# design.net
KiCad netlist of a schematic drawn in Altium Designer
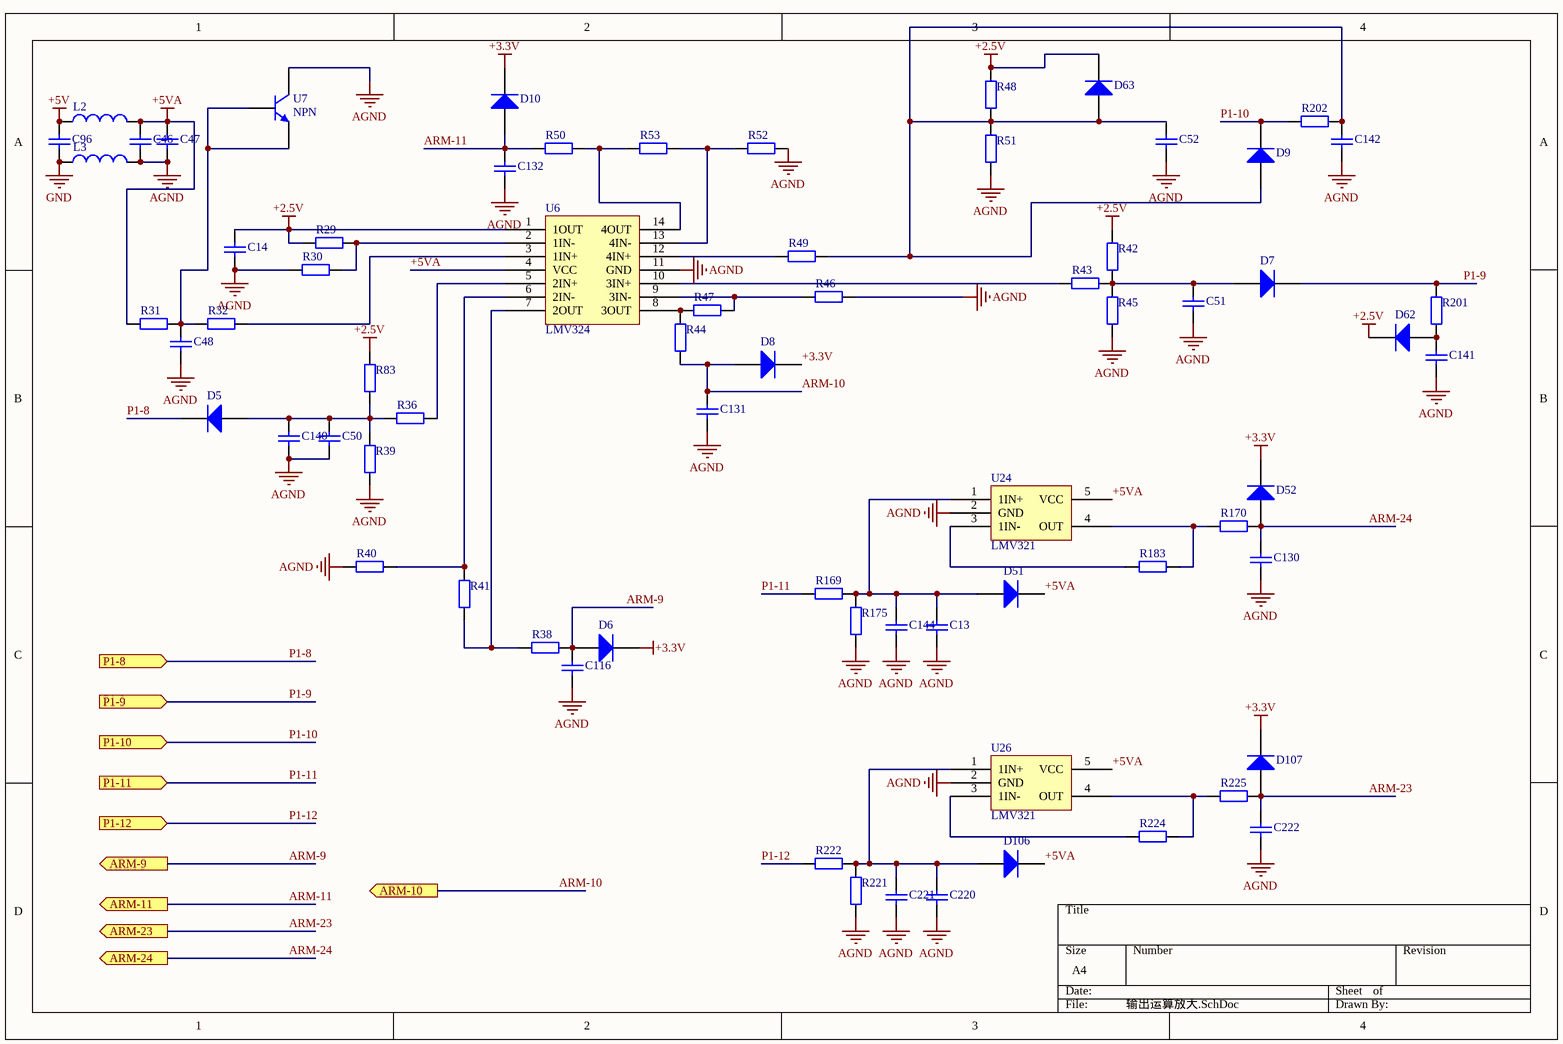
[diagram p0: 输出运算放大.SchDoc]

(export (version "E")
  (design (tool "Eeschema 10.0.6"))
  (components
    (comp (ref "C13")
      (value "Cap")
      (footprint "RAD-0.3")
      (description "Capacitor")
      (fields (field (name "PUBLISHER") "Altium Limited"))
      (libsource (lib "Miscellaneous Devices") (part "Cap"))
    )
    (comp (ref "C14")
      (value "Cap")
      (footprint "RAD-0.3")
      (description "Capacitor")
      (fields (field (name "PUBLISHER") "Altium Limited"))
      (libsource (lib "Miscellaneous Devices") (part "Cap"))
    )
    (comp (ref "C46")
      (value "Cap")
      (footprint "RAD-0.3")
      (description "Capacitor")
      (fields (field (name "PUBLISHER") "Altium Limited"))
      (libsource (lib "Miscellaneous Devices") (part "Cap"))
    )
    (comp (ref "C47")
      (value "Cap")
      (footprint "RAD-0.3")
      (description "Capacitor")
      (fields (field (name "PUBLISHER") "Altium Limited"))
      (libsource (lib "Miscellaneous Devices") (part "Cap"))
    )
    (comp (ref "C48")
      (value "Cap")
      (footprint "RAD-0.3")
      (description "Capacitor")
      (fields (field (name "PUBLISHER") "Altium Limited"))
      (libsource (lib "Miscellaneous Devices") (part "Cap"))
    )
    (comp (ref "C50")
      (value "Cap")
      (footprint "RAD-0.3")
      (description "Capacitor")
      (fields (field (name "PUBLISHER") "Altium Limited"))
      (libsource (lib "Miscellaneous Devices") (part "Cap"))
    )
    (comp (ref "C51")
      (value "Cap")
      (footprint "RAD-0.3")
      (description "Capacitor")
      (fields (field (name "PUBLISHER") "Altium Limited"))
      (libsource (lib "Miscellaneous Devices") (part "Cap"))
    )
    (comp (ref "C52")
      (value "Cap")
      (footprint "RAD-0.3")
      (description "Capacitor")
      (fields (field (name "PUBLISHER") "Altium Limited"))
      (libsource (lib "Miscellaneous Devices") (part "Cap"))
    )
    (comp (ref "C96")
      (value "Cap")
      (footprint "RAD-0.3")
      (description "Capacitor")
      (fields (field (name "PUBLISHER") "Altium Limited"))
      (libsource (lib "Miscellaneous Devices") (part "Cap"))
    )
    (comp (ref "C116")
      (value "Cap")
      (footprint "RAD-0.3")
      (description "Capacitor")
      (fields (field (name "PUBLISHER") "Altium Limited"))
      (libsource (lib "Miscellaneous Devices") (part "Cap"))
    )
    (comp (ref "C130")
      (value "Cap")
      (footprint "RAD-0.3")
      (description "Capacitor")
      (fields (field (name "PUBLISHER") "Altium Limited"))
      (libsource (lib "Miscellaneous Devices") (part "Cap"))
    )
    (comp (ref "C131")
      (value "Cap")
      (footprint "RAD-0.3")
      (description "Capacitor")
      (fields (field (name "PUBLISHER") "Altium Limited"))
      (libsource (lib "Miscellaneous Devices") (part "Cap"))
    )
    (comp (ref "C132")
      (value "Cap")
      (footprint "RAD-0.3")
      (description "Capacitor")
      (fields (field (name "PUBLISHER") "Altium Limited"))
      (libsource (lib "Miscellaneous Devices") (part "Cap"))
    )
    (comp (ref "C140")
      (value "Cap")
      (footprint "RAD-0.3")
      (description "Capacitor")
      (fields (field (name "PUBLISHER") "Altium Limited"))
      (libsource (lib "Miscellaneous Devices") (part "Cap"))
    )
    (comp (ref "C141")
      (value "Cap")
      (footprint "RAD-0.3")
      (description "Capacitor")
      (fields (field (name "PUBLISHER") "Altium Limited"))
      (libsource (lib "Miscellaneous Devices") (part "Cap"))
    )
    (comp (ref "C142")
      (value "Cap")
      (footprint "RAD-0.3")
      (description "Capacitor")
      (fields (field (name "PUBLISHER") "Altium Limited"))
      (libsource (lib "Miscellaneous Devices") (part "Cap"))
    )
    (comp (ref "C144")
      (value "Cap")
      (footprint "RAD-0.3")
      (description "Capacitor")
      (fields (field (name "PUBLISHER") "Altium Limited"))
      (libsource (lib "Miscellaneous Devices") (part "Cap"))
    )
    (comp (ref "C220")
      (value "Cap")
      (footprint "RAD-0.3")
      (description "Capacitor")
      (fields (field (name "PUBLISHER") "Altium Limited"))
      (libsource (lib "Miscellaneous Devices") (part "Cap"))
    )
    (comp (ref "C221")
      (value "Cap")
      (footprint "RAD-0.3")
      (description "Capacitor")
      (fields (field (name "PUBLISHER") "Altium Limited"))
      (libsource (lib "Miscellaneous Devices") (part "Cap"))
    )
    (comp (ref "C222")
      (value "Cap")
      (footprint "RAD-0.3")
      (description "Capacitor")
      (fields (field (name "PUBLISHER") "Altium Limited"))
      (libsource (lib "Miscellaneous Devices") (part "Cap"))
    )
    (comp (ref "D5")
      (value "Diode 1N4007")
      (footprint "DO-41")
      (description "1 Amp General Purpose Rectifier")
      (fields (field (name "PUBLISHER") "Altium Limited"))
      (libsource (lib "Miscellaneous Devices") (part "Diode 1N4007"))
    )
    (comp (ref "D6")
      (value "Diode 1N4007")
      (footprint "DO-41")
      (description "1 Amp General Purpose Rectifier")
      (fields (field (name "PUBLISHER") "Altium Limited"))
      (libsource (lib "Miscellaneous Devices") (part "Diode 1N4007"))
    )
    (comp (ref "D7")
      (value "Diode 1N4007")
      (footprint "DO-41")
      (description "1 Amp General Purpose Rectifier")
      (fields (field (name "PUBLISHER") "Altium Limited"))
      (libsource (lib "Miscellaneous Devices") (part "Diode 1N4007"))
    )
    (comp (ref "D8")
      (value "Diode 1N4007")
      (footprint "DO-41")
      (description "1 Amp General Purpose Rectifier")
      (fields (field (name "PUBLISHER") "Altium Limited"))
      (libsource (lib "Miscellaneous Devices") (part "Diode 1N4007"))
    )
    (comp (ref "D9")
      (value "Diode 1N4007")
      (footprint "DO-41")
      (description "1 Amp General Purpose Rectifier")
      (fields (field (name "PUBLISHER") "Altium Limited"))
      (libsource (lib "Miscellaneous Devices") (part "Diode 1N4007"))
    )
    (comp (ref "D10")
      (value "Diode 1N4007")
      (footprint "DO-41")
      (description "1 Amp General Purpose Rectifier")
      (fields (field (name "PUBLISHER") "Altium Limited"))
      (libsource (lib "Miscellaneous Devices") (part "Diode 1N4007"))
    )
    (comp (ref "D51")
      (value "Diode 1N4007")
      (footprint "DO-41")
      (description "1 Amp General Purpose Rectifier")
      (fields (field (name "PUBLISHER") "Altium Limited"))
      (libsource (lib "Miscellaneous Devices") (part "Diode 1N4007"))
    )
    (comp (ref "D52")
      (value "Diode 1N4007")
      (footprint "DO-41")
      (description "1 Amp General Purpose Rectifier")
      (fields (field (name "PUBLISHER") "Altium Limited"))
      (libsource (lib "Miscellaneous Devices") (part "Diode 1N4007"))
    )
    (comp (ref "D62")
      (value "Diode 1N4007")
      (footprint "DO-41")
      (description "1 Amp General Purpose Rectifier")
      (fields (field (name "PUBLISHER") "Altium Limited"))
      (libsource (lib "Miscellaneous Devices") (part "Diode 1N4007"))
    )
    (comp (ref "D63")
      (value "Diode 1N4007")
      (footprint "DO-41")
      (description "1 Amp General Purpose Rectifier")
      (fields (field (name "PUBLISHER") "Altium Limited"))
      (libsource (lib "Miscellaneous Devices") (part "Diode 1N4007"))
    )
    (comp (ref "D106")
      (value "Diode 1N4007")
      (footprint "DO-41")
      (description "1 Amp General Purpose Rectifier")
      (fields (field (name "PUBLISHER") "Altium Limited"))
      (libsource (lib "Miscellaneous Devices") (part "Diode 1N4007"))
    )
    (comp (ref "D107")
      (value "Diode 1N4007")
      (footprint "DO-41")
      (description "1 Amp General Purpose Rectifier")
      (fields (field (name "PUBLISHER") "Altium Limited"))
      (libsource (lib "Miscellaneous Devices") (part "Diode 1N4007"))
    )
    (comp (ref "L2")
      (value "Inductor")
      (footprint "0402-A")
      (fields (field (name "PUBLISHER") "Altium Limited"))
      (libsource (lib "Miscellaneous Devices") (part "Inductor"))
    )
    (comp (ref "L3")
      (value "Inductor")
      (footprint "0402-A")
      (fields (field (name "PUBLISHER") "Altium Limited"))
      (libsource (lib "Miscellaneous Devices") (part "Inductor"))
    )
    (comp (ref "R29")
      (value "Res2")
      (footprint "AXIAL-0.4")
      (description "Resistor")
      (fields (field (name "PUBLISHER") "Altium Limited"))
      (libsource (lib "") (part "Res2_1"))
    )
    (comp (ref "R30")
      (value "Res2")
      (footprint "AXIAL-0.4")
      (description "Resistor")
      (fields (field (name "PUBLISHER") "Altium Limited"))
      (libsource (lib "") (part "Res2_1"))
    )
    (comp (ref "R31")
      (value "Res2")
      (footprint "AXIAL-0.4")
      (description "Resistor")
      (fields (field (name "PUBLISHER") "Altium Limited"))
      (libsource (lib "") (part "Res2_1"))
    )
    (comp (ref "R32")
      (value "Res2")
      (footprint "AXIAL-0.4")
      (description "Resistor")
      (fields (field (name "PUBLISHER") "Altium Limited"))
      (libsource (lib "") (part "Res2_1"))
    )
    (comp (ref "R36")
      (value "Res2")
      (footprint "AXIAL-0.4")
      (description "Resistor")
      (fields (field (name "PUBLISHER") "Altium Limited"))
      (libsource (lib "") (part "Res2_1"))
    )
    (comp (ref "R38")
      (value "Res2")
      (footprint "AXIAL-0.4")
      (description "Resistor")
      (fields (field (name "PUBLISHER") "Altium Limited"))
      (libsource (lib "") (part "Res2_2"))
    )
    (comp (ref "R39")
      (value "Res2")
      (footprint "AXIAL-0.4")
      (description "Resistor")
      (fields (field (name "PUBLISHER") "Altium Limited"))
      (libsource (lib "Miscellaneous Devices") (part "Res2"))
    )
    (comp (ref "R40")
      (value "Res2")
      (footprint "AXIAL-0.4")
      (description "Resistor")
      (fields (field (name "PUBLISHER") "Altium Limited"))
      (libsource (lib "") (part "Res2_1"))
    )
    (comp (ref "R41")
      (value "Res2")
      (footprint "AXIAL-0.4")
      (description "Resistor")
      (fields (field (name "PUBLISHER") "Altium Limited"))
      (libsource (lib "Miscellaneous Devices") (part "Res2"))
    )
    (comp (ref "R42")
      (value "Res2")
      (footprint "AXIAL-0.4")
      (description "Resistor")
      (fields (field (name "PUBLISHER") "Altium Limited"))
      (libsource (lib "Miscellaneous Devices") (part "Res2"))
    )
    (comp (ref "R43")
      (value "Res2")
      (footprint "AXIAL-0.4")
      (description "Resistor")
      (fields (field (name "PUBLISHER") "Altium Limited"))
      (libsource (lib "") (part "Res2_1"))
    )
    (comp (ref "R44")
      (value "Res2")
      (footprint "AXIAL-0.4")
      (description "Resistor")
      (fields (field (name "PUBLISHER") "Altium Limited"))
      (libsource (lib "Miscellaneous Devices") (part "Res2"))
    )
    (comp (ref "R45")
      (value "Res2")
      (footprint "AXIAL-0.4")
      (description "Resistor")
      (fields (field (name "PUBLISHER") "Altium Limited"))
      (libsource (lib "Miscellaneous Devices") (part "Res2"))
    )
    (comp (ref "R46")
      (value "Res2")
      (footprint "AXIAL-0.4")
      (description "Resistor")
      (fields (field (name "PUBLISHER") "Altium Limited"))
      (libsource (lib "") (part "Res2_1"))
    )
    (comp (ref "R47")
      (value "Res2")
      (footprint "AXIAL-0.4")
      (description "Resistor")
      (fields (field (name "PUBLISHER") "Altium Limited"))
      (libsource (lib "") (part "Res2_1"))
    )
    (comp (ref "R48")
      (value "Res2")
      (footprint "AXIAL-0.4")
      (description "Resistor")
      (fields (field (name "PUBLISHER") "Altium Limited"))
      (libsource (lib "Miscellaneous Devices") (part "Res2"))
    )
    (comp (ref "R49")
      (value "Res2")
      (footprint "AXIAL-0.4")
      (description "Resistor")
      (fields (field (name "PUBLISHER") "Altium Limited"))
      (libsource (lib "") (part "Res2_1"))
    )
    (comp (ref "R50")
      (value "Res2")
      (footprint "AXIAL-0.4")
      (description "Resistor")
      (fields (field (name "PUBLISHER") "Altium Limited"))
      (libsource (lib "") (part "Res2_1"))
    )
    (comp (ref "R51")
      (value "Res2")
      (footprint "AXIAL-0.4")
      (description "Resistor")
      (fields (field (name "PUBLISHER") "Altium Limited"))
      (libsource (lib "Miscellaneous Devices") (part "Res2"))
    )
    (comp (ref "R52")
      (value "Res2")
      (footprint "AXIAL-0.4")
      (description "Resistor")
      (fields (field (name "PUBLISHER") "Altium Limited"))
      (libsource (lib "") (part "Res2_1"))
    )
    (comp (ref "R53")
      (value "Res2")
      (footprint "AXIAL-0.4")
      (description "Resistor")
      (fields (field (name "PUBLISHER") "Altium Limited"))
      (libsource (lib "") (part "Res2_1"))
    )
    (comp (ref "R83")
      (value "Res2")
      (footprint "AXIAL-0.4")
      (description "Resistor")
      (fields (field (name "PUBLISHER") "Altium Limited"))
      (libsource (lib "Miscellaneous Devices") (part "Res2"))
    )
    (comp (ref "R169")
      (value "Res2")
      (footprint "AXIAL-0.4")
      (description "Resistor")
      (fields (field (name "PUBLISHER") "Altium Limited"))
      (libsource (lib "") (part "Res2_1"))
    )
    (comp (ref "R170")
      (value "Res2")
      (footprint "AXIAL-0.4")
      (description "Resistor")
      (fields (field (name "PUBLISHER") "Altium Limited"))
      (libsource (lib "") (part "Res2_1"))
    )
    (comp (ref "R175")
      (value "Res2")
      (footprint "AXIAL-0.4")
      (description "Resistor")
      (fields (field (name "PUBLISHER") "Altium Limited"))
      (libsource (lib "Miscellaneous Devices") (part "Res2"))
    )
    (comp (ref "R183")
      (value "Res2")
      (footprint "AXIAL-0.4")
      (description "Resistor")
      (fields (field (name "PUBLISHER") "Altium Limited"))
      (libsource (lib "") (part "Res2_1"))
    )
    (comp (ref "R201")
      (value "Res2")
      (footprint "AXIAL-0.4")
      (description "Resistor")
      (fields (field (name "PUBLISHER") "Altium Limited"))
      (libsource (lib "Miscellaneous Devices") (part "Res2"))
    )
    (comp (ref "R202")
      (value "Res2")
      (footprint "AXIAL-0.4")
      (description "Resistor")
      (fields (field (name "PUBLISHER") "Altium Limited"))
      (libsource (lib "") (part "Res2_2"))
    )
    (comp (ref "R221")
      (value "Res2")
      (footprint "AXIAL-0.4")
      (description "Resistor")
      (fields (field (name "PUBLISHER") "Altium Limited"))
      (libsource (lib "Miscellaneous Devices") (part "Res2"))
    )
    (comp (ref "R222")
      (value "Res2")
      (footprint "AXIAL-0.4")
      (description "Resistor")
      (fields (field (name "PUBLISHER") "Altium Limited"))
      (libsource (lib "") (part "Res2_1"))
    )
    (comp (ref "R224")
      (value "Res2")
      (footprint "AXIAL-0.4")
      (description "Resistor")
      (fields (field (name "PUBLISHER") "Altium Limited"))
      (libsource (lib "") (part "Res2_1"))
    )
    (comp (ref "R225")
      (value "Res2")
      (footprint "AXIAL-0.4")
      (description "Resistor")
      (fields (field (name "PUBLISHER") "Altium Limited"))
      (libsource (lib "") (part "Res2_1"))
    )
    (comp (ref "U6") (value "LMV324") (libsource (lib "LMV324") (part "Component_1")))
    (comp (ref "U7")
      (value "NPN")
      (footprint "TO-226")
      (description "NPN Bipolar Transistor")
      (fields (field (name "PUBLISHER") "Altium Limited"))
      (libsource (lib "Miscellaneous Devices") (part "NPN"))
    )
    (comp (ref "U24") (value "LMV321") (libsource (lib "LMV321") (part "Component_1")))
    (comp (ref "U26") (value "LMV321") (libsource (lib "LMV321") (part "Component_1")))
  )
  (nets
    (net (code "1") (name "+2.5V") (class "Default")
      (node (ref "C14") (pin "2") (pinfunction "2_2") (pintype "passive"))
      (node (ref "D62") (pin "2") (pinfunction "K_2") (pintype "passive"))
      (node (ref "D63") (pin "2") (pinfunction "K_2") (pintype "passive"))
      (node (ref "R29") (pin "2") (pinfunction "2_2") (pintype "passive"))
      (node (ref "R42") (pin "1") (pinfunction "1_1") (pintype "passive"))
      (node (ref "R48") (pin "1") (pinfunction "1_1") (pintype "passive"))
      (node (ref "R83") (pin "1") (pinfunction "1_1") (pintype "passive"))
      (node (ref "U6") (pin "1") (pinfunction "1OUT_1") (pintype "passive"))
    )
    (net (code "2") (name "+3.3V") (class "Default")
      (node (ref "D10") (pin "2") (pinfunction "K_2") (pintype "passive"))
      (node (ref "D107") (pin "2") (pinfunction "K_2") (pintype "passive"))
      (node (ref "D52") (pin "2") (pinfunction "K_2") (pintype "passive"))
      (node (ref "D6") (pin "2") (pinfunction "K_2") (pintype "passive"))
      (node (ref "D8") (pin "2") (pinfunction "K_2") (pintype "passive"))
    )
    (net (code "3") (name "+5V") (class "Default")
      (node (ref "C96") (pin "2") (pinfunction "2_2") (pintype "passive"))
      (node (ref "L2") (pin "1") (pinfunction "1_1") (pintype "passive"))
    )
    (net (code "4") (name "+5VA") (class "Default")
      (node (ref "C46") (pin "2") (pinfunction "2_2") (pintype "passive"))
      (node (ref "C47") (pin "2") (pinfunction "2_2") (pintype "passive"))
      (node (ref "D106") (pin "2") (pinfunction "K_2") (pintype "passive"))
      (node (ref "D51") (pin "2") (pinfunction "K_2") (pintype "passive"))
      (node (ref "L2") (pin "2") (pinfunction "2_2") (pintype "passive"))
      (node (ref "R31") (pin "2") (pinfunction "2_2") (pintype "passive"))
      (node (ref "U24") (pin "5") (pinfunction "VCC_5") (pintype "passive"))
      (node (ref "U26") (pin "5") (pinfunction "VCC_5") (pintype "passive"))
      (node (ref "U6") (pin "4") (pinfunction "VCC_4") (pintype "passive"))
    )
    (net (code "5") (name "/ARM-9") (class "Default")
      (node (ref "C116") (pin "2") (pinfunction "2_2") (pintype "passive"))
      (node (ref "D6") (pin "1") (pinfunction "A_1") (pintype "passive"))
      (node (ref "R38") (pin "2") (pinfunction "2_2") (pintype "passive"))
    )
    (net (code "6") (name "/ARM-10") (class "Default")
      (node (ref "C131") (pin "2") (pinfunction "2_2") (pintype "passive"))
      (node (ref "D8") (pin "1") (pinfunction "A_1") (pintype "passive"))
      (node (ref "R44") (pin "2") (pinfunction "2_2") (pintype "passive"))
    )
    (net (code "7") (name "/ARM-11") (class "Default")
      (node (ref "C132") (pin "2") (pinfunction "2_2") (pintype "passive"))
      (node (ref "D10") (pin "1") (pinfunction "A_1") (pintype "passive"))
      (node (ref "R50") (pin "2") (pinfunction "2_2") (pintype "passive"))
    )
    (net (code "8") (name "/ARM-23") (class "Default")
      (node (ref "C222") (pin "2") (pinfunction "2_2") (pintype "passive"))
      (node (ref "D107") (pin "1") (pinfunction "A_1") (pintype "passive"))
      (node (ref "R225") (pin "1") (pinfunction "1_1") (pintype "passive"))
    )
    (net (code "9") (name "/ARM-24") (class "Default")
      (node (ref "C130") (pin "2") (pinfunction "2_2") (pintype "passive"))
      (node (ref "D52") (pin "1") (pinfunction "A_1") (pintype "passive"))
      (node (ref "R170") (pin "1") (pinfunction "1_1") (pintype "passive"))
    )
    (net (code "10") (name "/P1-8") (class "Default")
      (node (ref "D5") (pin "2") (pinfunction "K_2") (pintype "passive"))
    )
    (net (code "11") (name "/P1-9") (class "Default")
      (node (ref "D7") (pin "2") (pinfunction "K_2") (pintype "passive"))
      (node (ref "R201") (pin "1") (pinfunction "1_1") (pintype "passive"))
    )
    (net (code "12") (name "/P1-10") (class "Default")
      (node (ref "D9") (pin "2") (pinfunction "K_2") (pintype "passive"))
      (node (ref "R202") (pin "1") (pinfunction "1_1") (pintype "passive"))
    )
    (net (code "13") (name "/P1-11") (class "Default")
      (node (ref "R169") (pin "2") (pinfunction "2_2") (pintype "passive"))
    )
    (net (code "14") (name "/P1-12") (class "Default")
      (node (ref "R222") (pin "2") (pinfunction "2_2") (pintype "passive"))
    )
    (net (code "15") (name "AGND") (class "Default")
      (node (ref "C116") (pin "1") (pinfunction "1_1") (pintype "passive"))
      (node (ref "C13") (pin "1") (pinfunction "1_1") (pintype "passive"))
      (node (ref "C130") (pin "1") (pinfunction "1_1") (pintype "passive"))
      (node (ref "C131") (pin "1") (pinfunction "1_1") (pintype "passive"))
      (node (ref "C132") (pin "1") (pinfunction "1_1") (pintype "passive"))
      (node (ref "C14") (pin "1") (pinfunction "1_1") (pintype "passive"))
      (node (ref "C140") (pin "1") (pinfunction "1_1") (pintype "passive"))
      (node (ref "C141") (pin "1") (pinfunction "1_1") (pintype "passive"))
      (node (ref "C142") (pin "1") (pinfunction "1_1") (pintype "passive"))
      (node (ref "C144") (pin "1") (pinfunction "1_1") (pintype "passive"))
      (node (ref "C220") (pin "1") (pinfunction "1_1") (pintype "passive"))
      (node (ref "C221") (pin "1") (pinfunction "1_1") (pintype "passive"))
      (node (ref "C222") (pin "1") (pinfunction "1_1") (pintype "passive"))
      (node (ref "C46") (pin "1") (pinfunction "1_1") (pintype "passive"))
      (node (ref "C47") (pin "1") (pinfunction "1_1") (pintype "passive"))
      (node (ref "C48") (pin "1") (pinfunction "1_1") (pintype "passive"))
      (node (ref "C50") (pin "1") (pinfunction "1_1") (pintype "passive"))
      (node (ref "C51") (pin "1") (pinfunction "1_1") (pintype "passive"))
      (node (ref "C52") (pin "1") (pinfunction "1_1") (pintype "passive"))
      (node (ref "L3") (pin "2") (pinfunction "2_2") (pintype "passive"))
      (node (ref "R175") (pin "2") (pinfunction "2_2") (pintype "passive"))
      (node (ref "R221") (pin "2") (pinfunction "2_2") (pintype "passive"))
      (node (ref "R30") (pin "2") (pinfunction "2_2") (pintype "passive"))
      (node (ref "R39") (pin "2") (pinfunction "2_2") (pintype "passive"))
      (node (ref "R40") (pin "2") (pinfunction "2_2") (pintype "passive"))
      (node (ref "R45") (pin "2") (pinfunction "2_2") (pintype "passive"))
      (node (ref "R46") (pin "1") (pinfunction "1_1") (pintype "passive"))
      (node (ref "R51") (pin "2") (pinfunction "2_2") (pintype "passive"))
      (node (ref "R52") (pin "1") (pinfunction "1_1") (pintype "passive"))
      (node (ref "U24") (pin "2") (pinfunction "GND_2") (pintype "passive"))
      (node (ref "U26") (pin "2") (pinfunction "GND_2") (pintype "passive"))
      (node (ref "U6") (pin "11") (pinfunction "GND_11") (pintype "passive"))
      (node (ref "U7") (pin "1") (pinfunction "C_1") (pintype "passive"))
    )
    (net (code "16") (name "GND") (class "Default")
      (node (ref "C96") (pin "1") (pinfunction "1_1") (pintype "passive"))
      (node (ref "L3") (pin "1") (pinfunction "1_1") (pintype "passive"))
    )
    (net (code "17") (name "Net-(D5-A)") (class "Default")
      (node (ref "C140") (pin "2") (pinfunction "2_2") (pintype "passive"))
      (node (ref "C50") (pin "2") (pinfunction "2_2") (pintype "passive"))
      (node (ref "D5") (pin "1") (pinfunction "A_1") (pintype "passive"))
      (node (ref "R36") (pin "2") (pinfunction "2_2") (pintype "passive"))
      (node (ref "R39") (pin "1") (pinfunction "1_1") (pintype "passive"))
      (node (ref "R83") (pin "2") (pinfunction "2_2") (pintype "passive"))
    )
    (net (code "18") (name "Net-(D7-A)") (class "Default")
      (node (ref "C51") (pin "2") (pinfunction "2_2") (pintype "passive"))
      (node (ref "D7") (pin "1") (pinfunction "A_1") (pintype "passive"))
      (node (ref "R42") (pin "2") (pinfunction "2_2") (pintype "passive"))
      (node (ref "R43") (pin "1") (pinfunction "1_1") (pintype "passive"))
      (node (ref "R45") (pin "1") (pinfunction "1_1") (pintype "passive"))
    )
    (net (code "19") (name "Net-(D51-A)") (class "Default")
      (node (ref "C13") (pin "2") (pinfunction "2_2") (pintype "passive"))
      (node (ref "C144") (pin "2") (pinfunction "2_2") (pintype "passive"))
      (node (ref "D51") (pin "1") (pinfunction "A_1") (pintype "passive"))
      (node (ref "R169") (pin "1") (pinfunction "1_1") (pintype "passive"))
      (node (ref "R175") (pin "1") (pinfunction "1_1") (pintype "passive"))
      (node (ref "U24") (pin "1") (pinfunction "1IN+_1") (pintype "passive"))
    )
    (net (code "20") (name "Net-(D62-A)") (class "Default")
      (node (ref "C141") (pin "2") (pinfunction "2_2") (pintype "passive"))
      (node (ref "D62") (pin "1") (pinfunction "A_1") (pintype "passive"))
      (node (ref "R201") (pin "2") (pinfunction "2_2") (pintype "passive"))
    )
    (net (code "21") (name "Net-(D63-A)") (class "Default")
      (node (ref "C142") (pin "2") (pinfunction "2_2") (pintype "passive"))
      (node (ref "C52") (pin "2") (pinfunction "2_2") (pintype "passive"))
      (node (ref "D63") (pin "1") (pinfunction "A_1") (pintype "passive"))
      (node (ref "D9") (pin "1") (pinfunction "A_1") (pintype "passive"))
      (node (ref "R202") (pin "2") (pinfunction "2_2") (pintype "passive"))
      (node (ref "R48") (pin "2") (pinfunction "2_2") (pintype "passive"))
      (node (ref "R49") (pin "1") (pinfunction "1_1") (pintype "passive"))
      (node (ref "R51") (pin "1") (pinfunction "1_1") (pintype "passive"))
    )
    (net (code "22") (name "Net-(D106-A)") (class "Default")
      (node (ref "C220") (pin "2") (pinfunction "2_2") (pintype "passive"))
      (node (ref "C221") (pin "2") (pinfunction "2_2") (pintype "passive"))
      (node (ref "D106") (pin "1") (pinfunction "A_1") (pintype "passive"))
      (node (ref "R221") (pin "1") (pinfunction "1_1") (pintype "passive"))
      (node (ref "R222") (pin "1") (pinfunction "1_1") (pintype "passive"))
      (node (ref "U26") (pin "1") (pinfunction "1IN+_1") (pintype "passive"))
    )
    (net (code "23") (name "Net-(U6-1IN+)") (class "Default")
      (node (ref "R32") (pin "1") (pinfunction "1_1") (pintype "passive"))
      (node (ref "U6") (pin "3") (pinfunction "1IN+_3") (pintype "passive"))
    )
    (net (code "24") (name "Net-(U6-1IN-)") (class "Default")
      (node (ref "R29") (pin "1") (pinfunction "1_1") (pintype "passive"))
      (node (ref "R30") (pin "1") (pinfunction "1_1") (pintype "passive"))
      (node (ref "U6") (pin "2") (pinfunction "1IN-_2") (pintype "passive"))
    )
    (net (code "25") (name "Net-(U6-2IN+)") (class "Default")
      (node (ref "R36") (pin "1") (pinfunction "1_1") (pintype "passive"))
      (node (ref "U6") (pin "5") (pinfunction "2IN+_5") (pintype "passive"))
    )
    (net (code "26") (name "Net-(U6-2IN-)") (class "Default")
      (node (ref "R40") (pin "1") (pinfunction "1_1") (pintype "passive"))
      (node (ref "R41") (pin "1") (pinfunction "1_1") (pintype "passive"))
      (node (ref "U6") (pin "6") (pinfunction "2IN-_6") (pintype "passive"))
    )
    (net (code "27") (name "Net-(U6-2OUT)") (class "Default")
      (node (ref "R38") (pin "1") (pinfunction "1_1") (pintype "passive"))
      (node (ref "R41") (pin "2") (pinfunction "2_2") (pintype "passive"))
      (node (ref "U6") (pin "7") (pinfunction "2OUT_7") (pintype "passive"))
    )
    (net (code "28") (name "Net-(U6-3IN+)") (class "Default")
      (node (ref "R43") (pin "2") (pinfunction "2_2") (pintype "passive"))
      (node (ref "U6") (pin "10") (pinfunction "3IN+_10") (pintype "passive"))
    )
    (net (code "29") (name "Net-(U6-3IN-)") (class "Default")
      (node (ref "R46") (pin "2") (pinfunction "2_2") (pintype "passive"))
      (node (ref "R47") (pin "1") (pinfunction "1_1") (pintype "passive"))
      (node (ref "U6") (pin "9") (pinfunction "3IN-_9") (pintype "passive"))
    )
    (net (code "30") (name "Net-(U6-3OUT)") (class "Default")
      (node (ref "R44") (pin "1") (pinfunction "1_1") (pintype "passive"))
      (node (ref "R47") (pin "2") (pinfunction "2_2") (pintype "passive"))
      (node (ref "U6") (pin "8") (pinfunction "3OUT_8") (pintype "passive"))
    )
    (net (code "31") (name "Net-(U6-4IN+)") (class "Default")
      (node (ref "R49") (pin "2") (pinfunction "2_2") (pintype "passive"))
      (node (ref "U6") (pin "12") (pinfunction "4IN+_12") (pintype "passive"))
    )
    (net (code "32") (name "Net-(U6-4IN-)") (class "Default")
      (node (ref "R52") (pin "2") (pinfunction "2_2") (pintype "passive"))
      (node (ref "R53") (pin "1") (pinfunction "1_1") (pintype "passive"))
      (node (ref "U6") (pin "13") (pinfunction "4IN-_13") (pintype "passive"))
    )
    (net (code "33") (name "Net-(U6-4OUT)") (class "Default")
      (node (ref "R50") (pin "1") (pinfunction "1_1") (pintype "passive"))
      (node (ref "R53") (pin "2") (pinfunction "2_2") (pintype "passive"))
      (node (ref "U6") (pin "14") (pinfunction "4OUT_14") (pintype "passive"))
    )
    (net (code "34") (name "Net-(U7-B)") (class "Default")
      (node (ref "C48") (pin "2") (pinfunction "2_2") (pintype "passive"))
      (node (ref "R31") (pin "1") (pinfunction "1_1") (pintype "passive"))
      (node (ref "R32") (pin "2") (pinfunction "2_2") (pintype "passive"))
      (node (ref "U7") (pin "2") (pinfunction "B_2") (pintype "passive"))
      (node (ref "U7") (pin "3") (pinfunction "E_3") (pintype "passive"))
    )
    (net (code "35") (name "Net-(U24-1IN-)") (class "Default")
      (node (ref "R183") (pin "2") (pinfunction "2_2") (pintype "passive"))
      (node (ref "U24") (pin "3") (pinfunction "1IN-_3") (pintype "passive"))
    )
    (net (code "36") (name "Net-(U24-OUT)") (class "Default")
      (node (ref "R170") (pin "2") (pinfunction "2_2") (pintype "passive"))
      (node (ref "R183") (pin "1") (pinfunction "1_1") (pintype "passive"))
      (node (ref "U24") (pin "4") (pinfunction "OUT_4") (pintype "passive"))
    )
    (net (code "37") (name "Net-(U26-1IN-)") (class "Default")
      (node (ref "R224") (pin "2") (pinfunction "2_2") (pintype "passive"))
      (node (ref "U26") (pin "3") (pinfunction "1IN-_3") (pintype "passive"))
    )
    (net (code "38") (name "Net-(U26-OUT)") (class "Default")
      (node (ref "R224") (pin "1") (pinfunction "1_1") (pintype "passive"))
      (node (ref "R225") (pin "2") (pinfunction "2_2") (pintype "passive"))
      (node (ref "U26") (pin "4") (pinfunction "OUT_4") (pintype "passive"))
    )
  )
)
